# MATE_2024_float_layer_cake_footprint_v1.net
KiCad netlist of a schematic drawn in EAGLE
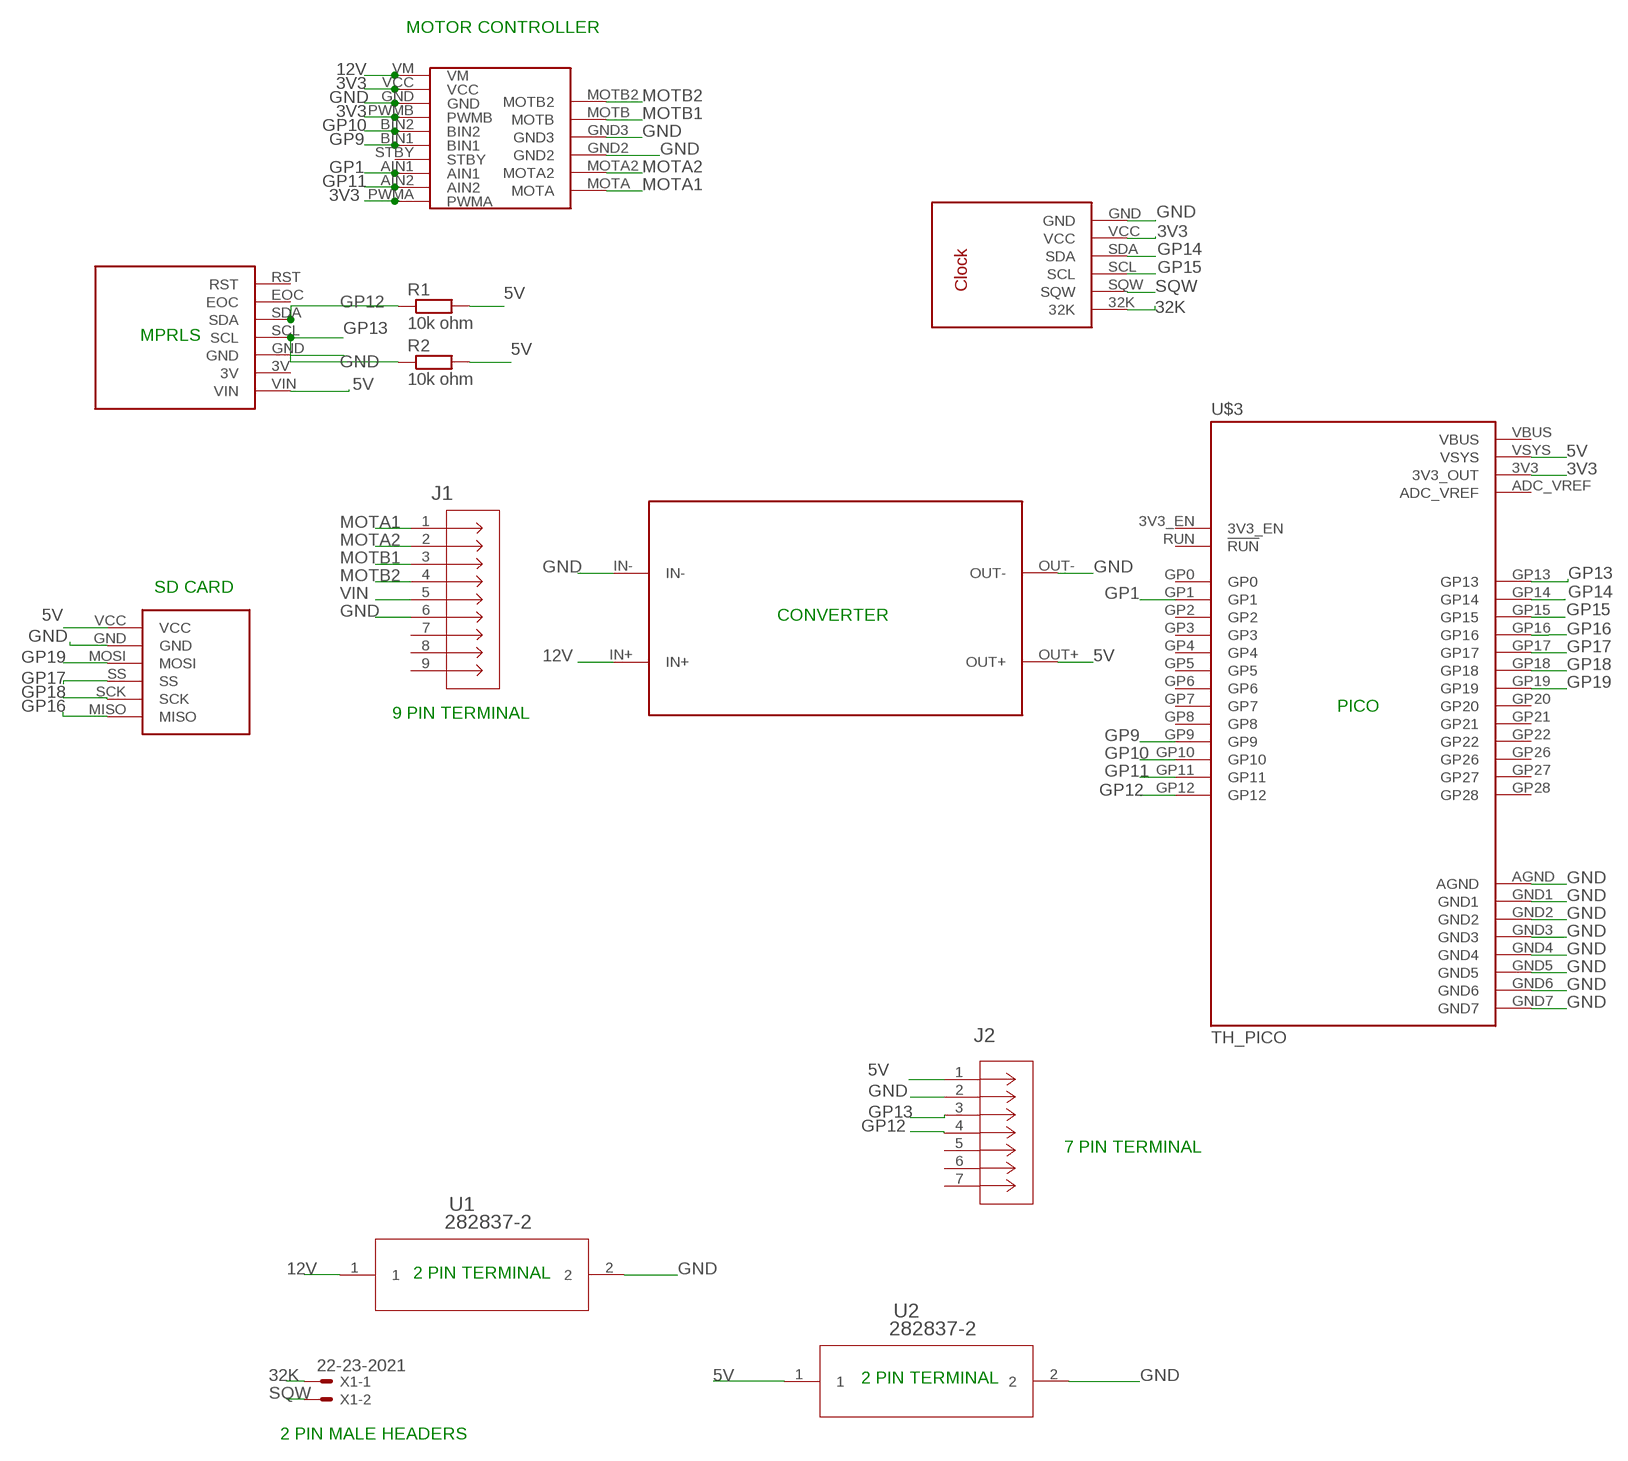
[diagram p0: schematic, sheet 1]

(export (version "E")
  (design (tool "Eeschema 10.0.6"))
  (components
    (comp (ref "J1")
      (value "282837-9")
      (footprint "eagle-import:CONN9_282837-9_TEC")
      (fields (field (name "COPYRIGHT") "Copyright (C) 2024 Ultra Librarian. All rights reserved."))
      (libsource (lib "eagle-import") (part "282837-9"))
    )
    (comp (ref "J2")
      (value "282837-7")
      (footprint "eagle-import:282837-7_TEC")
      (fields (field (name "COPYRIGHT") "Copyright (C) 2024 Ultra Librarian. All rights reserved."))
      (libsource (lib "eagle-import") (part "282837-7"))
    )
    (comp (ref "PRESSURE")
      (value "PRESSURE")
      (footprint "eagle-import:PRESSURE")
      (libsource (lib "eagle-import") (part "PRESSURE"))
    )
    (comp (ref "R1")
      (value "10k ohm")
      (footprint "eagle-import:0204_7")
      (libsource (lib "eagle-import") (part "R-EU_0204/7"))
    )
    (comp (ref "R2")
      (value "10k ohm")
      (footprint "eagle-import:0204_7")
      (libsource (lib "eagle-import") (part "R-EU_0204/7"))
    )
    (comp (ref "U$1")
      (value "CONVERTER")
      (footprint "eagle-import:CONVERTER")
      (libsource (lib "eagle-import") (part "CONVERTER"))
    )
    (comp (ref "U$2")
      (value "STEPPERMOTOR")
      (footprint "eagle-import:STEPPERV2")
      (libsource (lib "eagle-import") (part "STEPPERMOTOR"))
    )
    (comp (ref "U$3")
      (value "TH_PICO")
      (footprint "eagle-import:TH_PICO")
      (libsource (lib "eagle-import") (part "TH_PICO"))
    )
    (comp (ref "U$5")
      (value "MICROSDCARD")
      (footprint "eagle-import:MICROSDCARD")
      (libsource (lib "eagle-import") (part "MICROSDCARD"))
    )
    (comp (ref "U$6")
      (value "CLOCKMODULE")
      (footprint "eagle-import:CLOCKMODULE")
      (libsource (lib "eagle-import") (part "CLOCKMODULE"))
    )
    (comp (ref "U1")
      (value "282837-2")
      (footprint "eagle-import:282837-2_TYC")
      (fields (field (name "COPYRIGHT") "Copyright (C) 2024 Ultra Librarian. All rights reserved."))
      (libsource (lib "eagle-import") (part "282837-2"))
    )
    (comp (ref "U2")
      (value "282837-2")
      (footprint "eagle-import:282837-2_TYC")
      (fields (field (name "COPYRIGHT") "Copyright (C) 2024 Ultra Librarian. All rights reserved."))
      (libsource (lib "eagle-import") (part "282837-2"))
    )
    (comp (ref "X1")
      (value "22-23-2021")
      (footprint "eagle-import:22-23-2021")
      (fields (field (name "MF") "MOLEX"))
      (libsource (lib "eagle-import") (part "22-23-2021"))
    )
  )
  (nets
    (net (code "1") (name "/3V3") (class "Default")
      (node (ref "U$2") (pin "PWMA") (pinfunction "PWMA_PWMA") (pintype "bidirectional"))
      (node (ref "U$2") (pin "PWMB") (pinfunction "PWMB_PWMB") (pintype "bidirectional"))
      (node (ref "U$2") (pin "VCC") (pinfunction "VCC_VCC") (pintype "bidirectional"))
      (node (ref "U$3") (pin "3V3") (pinfunction "3V3_OUT_3V3") (pintype "power_in"))
      (node (ref "U$6") (pin "VCC") (pinfunction "VCC_VCC") (pintype "bidirectional"))
    )
    (net (code "2") (name "/5V") (class "Default")
      (node (ref "J2") (pin "1") (pinfunction "1_1") (pintype "passive"))
      (node (ref "PRESSURE") (pin "VIN") (pinfunction "VIN_VIN") (pintype "bidirectional"))
      (node (ref "R1") (pin "2") (pinfunction "2_2") (pintype "passive"))
      (node (ref "R2") (pin "2") (pinfunction "2_2") (pintype "passive"))
      (node (ref "U$1") (pin "OUT+") (pinfunction "OUT+_OUT+") (pintype "bidirectional"))
      (node (ref "U$3") (pin "VSYS") (pinfunction "VSYS_VSYS") (pintype "power_in"))
      (node (ref "U$5") (pin "VCC") (pinfunction "VCC_VCC") (pintype "bidirectional"))
      (node (ref "U2") (pin "1") (pinfunction "1_1") (pintype "passive"))
    )
    (net (code "3") (name "/12V") (class "Default")
      (node (ref "U$1") (pin "IN+") (pinfunction "IN+_IN+") (pintype "bidirectional"))
      (node (ref "U$2") (pin "VM") (pinfunction "VM_VM") (pintype "bidirectional"))
      (node (ref "U1") (pin "1") (pinfunction "1_1") (pintype "passive"))
    )
    (net (code "4") (name "/32K") (class "Default")
      (node (ref "U$6") (pin "32K") (pinfunction "32K_32K") (pintype "bidirectional"))
      (node (ref "X1") (pin "1") (pinfunction "S_1") (pintype "passive"))
    )
    (net (code "5") (name "/ADC_VREF") (class "Default")
      (node (ref "U$3") (pin "ADC_VREF") (pinfunction "ADC_VREF_ADC_VREF") (pintype "power_in"))
    )
    (net (code "6") (name "/GND") (class "Default")
      (node (ref "J1") (pin "6") (pinfunction "6_6") (pintype "passive"))
      (node (ref "J2") (pin "2") (pinfunction "2_2") (pintype "passive"))
      (node (ref "PRESSURE") (pin "GND") (pinfunction "GND_GND") (pintype "bidirectional"))
      (node (ref "U$1") (pin "IN-") (pinfunction "IN-_IN-") (pintype "bidirectional"))
      (node (ref "U$1") (pin "OUT-") (pinfunction "OUT-_OUT-") (pintype "bidirectional"))
      (node (ref "U$2") (pin "GND") (pinfunction "GND_GND") (pintype "bidirectional"))
      (node (ref "U$2") (pin "GND2") (pinfunction "GND2_GND2") (pintype "bidirectional"))
      (node (ref "U$2") (pin "GND3") (pinfunction "GND3_GND3") (pintype "bidirectional"))
      (node (ref "U$3") (pin "AGND") (pinfunction "AGND_AGND") (pintype "power_in"))
      (node (ref "U$3") (pin "GND1") (pinfunction "GND1_GND1") (pintype "power_in"))
      (node (ref "U$3") (pin "GND2") (pinfunction "GND2_GND2") (pintype "power_in"))
      (node (ref "U$3") (pin "GND3") (pinfunction "GND3_GND3") (pintype "power_in"))
      (node (ref "U$3") (pin "GND4") (pinfunction "GND4_GND4") (pintype "power_in"))
      (node (ref "U$3") (pin "GND5") (pinfunction "GND5_GND5") (pintype "power_in"))
      (node (ref "U$3") (pin "GND6") (pinfunction "GND6_GND6") (pintype "power_in"))
      (node (ref "U$3") (pin "GND7") (pinfunction "GND7_GND7") (pintype "power_in"))
      (node (ref "U$5") (pin "GND") (pinfunction "GND_GND") (pintype "bidirectional"))
      (node (ref "U$6") (pin "GND") (pinfunction "GND_GND") (pintype "bidirectional"))
      (node (ref "U1") (pin "2") (pinfunction "2_2") (pintype "passive"))
      (node (ref "U2") (pin "2") (pinfunction "2_2") (pintype "passive"))
    )
    (net (code "7") (name "/GP1") (class "Default")
      (node (ref "U$2") (pin "AIN1") (pinfunction "AIN1_AIN1") (pintype "bidirectional"))
      (node (ref "U$3") (pin "GP1") (pinfunction "GP1_GP1") (pintype "bidirectional"))
    )
    (net (code "8") (name "/GP9") (class "Default")
      (node (ref "U$2") (pin "BIN1") (pinfunction "BIN1_BIN1") (pintype "bidirectional"))
      (node (ref "U$3") (pin "GP9") (pinfunction "GP9_GP9") (pintype "bidirectional"))
    )
    (net (code "9") (name "/GP10") (class "Default")
      (node (ref "U$2") (pin "BIN2") (pinfunction "BIN2_BIN2") (pintype "bidirectional"))
      (node (ref "U$3") (pin "GP10") (pinfunction "GP10_GP10") (pintype "bidirectional"))
    )
    (net (code "10") (name "/GP11") (class "Default")
      (node (ref "U$2") (pin "AIN2") (pinfunction "AIN2_AIN2") (pintype "bidirectional"))
      (node (ref "U$3") (pin "GP11") (pinfunction "GP11_GP11") (pintype "bidirectional"))
    )
    (net (code "11") (name "/GP12") (class "Default")
      (node (ref "J2") (pin "4") (pinfunction "4_4") (pintype "passive"))
      (node (ref "PRESSURE") (pin "SDA") (pinfunction "SDA_SDA") (pintype "bidirectional"))
      (node (ref "R1") (pin "1") (pinfunction "1_1") (pintype "passive"))
      (node (ref "U$3") (pin "GP12") (pinfunction "GP12_GP12") (pintype "bidirectional"))
    )
    (net (code "12") (name "/GP13") (class "Default")
      (node (ref "J2") (pin "3") (pinfunction "3_3") (pintype "passive"))
      (node (ref "PRESSURE") (pin "SCL") (pinfunction "SCL_SCL") (pintype "bidirectional"))
      (node (ref "R2") (pin "1") (pinfunction "1_1") (pintype "passive"))
      (node (ref "U$3") (pin "GP13") (pinfunction "GP13_GP13") (pintype "bidirectional"))
    )
    (net (code "13") (name "/GP14") (class "Default")
      (node (ref "U$3") (pin "GP14") (pinfunction "GP14_GP14") (pintype "bidirectional"))
      (node (ref "U$6") (pin "SDA") (pinfunction "SDA_SDA") (pintype "bidirectional"))
    )
    (net (code "14") (name "/GP15") (class "Default")
      (node (ref "U$3") (pin "GP15") (pinfunction "GP15_GP15") (pintype "bidirectional"))
      (node (ref "U$6") (pin "SCL") (pinfunction "SCL_SCL") (pintype "bidirectional"))
    )
    (net (code "15") (name "/GP16") (class "Default")
      (node (ref "U$3") (pin "GP16") (pinfunction "GP16_GP16") (pintype "bidirectional"))
      (node (ref "U$5") (pin "MISO") (pinfunction "MISO_MISO") (pintype "bidirectional"))
    )
    (net (code "16") (name "/GP17") (class "Default")
      (node (ref "U$3") (pin "GP17") (pinfunction "GP17_GP17") (pintype "bidirectional"))
      (node (ref "U$5") (pin "SS") (pinfunction "SS_SS") (pintype "bidirectional"))
    )
    (net (code "17") (name "/GP18") (class "Default")
      (node (ref "U$3") (pin "GP18") (pinfunction "GP18_GP18") (pintype "bidirectional"))
      (node (ref "U$5") (pin "SCK") (pinfunction "SCK_SCK") (pintype "bidirectional"))
    )
    (net (code "18") (name "/GP19") (class "Default")
      (node (ref "U$3") (pin "GP19") (pinfunction "GP19_GP19") (pintype "bidirectional"))
      (node (ref "U$5") (pin "MOSI") (pinfunction "MOSI_MOSI") (pintype "bidirectional"))
    )
    (net (code "19") (name "/MOTA1") (class "Default")
      (node (ref "J1") (pin "1") (pinfunction "1_1") (pintype "passive"))
      (node (ref "U$2") (pin "MOTA") (pinfunction "MOTA_MOTA") (pintype "bidirectional"))
    )
    (net (code "20") (name "/MOTA2") (class "Default")
      (node (ref "J1") (pin "2") (pinfunction "2_2") (pintype "passive"))
      (node (ref "U$2") (pin "MOTA2") (pinfunction "MOTA2_MOTA2") (pintype "bidirectional"))
    )
    (net (code "21") (name "/MOTB1") (class "Default")
      (node (ref "J1") (pin "3") (pinfunction "3_3") (pintype "passive"))
      (node (ref "U$2") (pin "MOTB") (pinfunction "MOTB_MOTB") (pintype "bidirectional"))
    )
    (net (code "22") (name "/MOTB2") (class "Default")
      (node (ref "J1") (pin "4") (pinfunction "4_4") (pintype "passive"))
      (node (ref "U$2") (pin "MOTB2") (pinfunction "MOTB2_MOTB2") (pintype "bidirectional"))
    )
    (net (code "23") (name "/SQW") (class "Default")
      (node (ref "U$6") (pin "SQW") (pinfunction "SQW_SQW") (pintype "bidirectional"))
      (node (ref "X1") (pin "2") (pinfunction "S_2") (pintype "passive"))
    )
    (net (code "24") (name "/VBUS") (class "Default")
      (node (ref "U$3") (pin "VBUS") (pinfunction "VBUS_VBUS") (pintype "power_in"))
    )
    (net (code "25") (name "/VIN") (class "Default")
      (node (ref "J1") (pin "5") (pinfunction "5_5") (pintype "passive"))
    )
    (net (code "26") (name "unconnected-(J1-Pad7)") (class "Default")
      (node (ref "J1") (pin "7") (pinfunction "7_7") (pintype "passive"))
    )
    (net (code "27") (name "unconnected-(J1-Pad8)") (class "Default")
      (node (ref "J1") (pin "8") (pinfunction "8_8") (pintype "passive"))
    )
    (net (code "28") (name "unconnected-(J1-Pad9)") (class "Default")
      (node (ref "J1") (pin "9") (pinfunction "9_9") (pintype "passive"))
    )
    (net (code "29") (name "unconnected-(J2-Pad5)") (class "Default")
      (node (ref "J2") (pin "5") (pinfunction "5_5") (pintype "passive"))
    )
    (net (code "30") (name "unconnected-(J2-Pad6)") (class "Default")
      (node (ref "J2") (pin "6") (pinfunction "6_6") (pintype "passive"))
    )
    (net (code "31") (name "unconnected-(J2-Pad7)") (class "Default")
      (node (ref "J2") (pin "7") (pinfunction "7_7") (pintype "passive"))
    )
    (net (code "32") (name "unconnected-(PRESSURE-Pad3V)") (class "Default")
      (node (ref "PRESSURE") (pin "3V") (pinfunction "3V_3V") (pintype "bidirectional"))
    )
    (net (code "33") (name "unconnected-(PRESSURE-PadEOC)") (class "Default")
      (node (ref "PRESSURE") (pin "EOC") (pinfunction "EOC_EOC") (pintype "bidirectional"))
    )
    (net (code "34") (name "unconnected-(PRESSURE-PadRST)") (class "Default")
      (node (ref "PRESSURE") (pin "RST") (pinfunction "RST_RST") (pintype "bidirectional"))
    )
    (net (code "35") (name "unconnected-(U$2-PadSTBY)") (class "Default")
      (node (ref "U$2") (pin "STBY") (pinfunction "STBY_STBY") (pintype "bidirectional"))
    )
    (net (code "36") (name "unconnected-(U$3-Pad3V3_EN)") (class "Default")
      (node (ref "U$3") (pin "3V3_EN") (pinfunction "3V3_EN_3V3_EN") (pintype "input"))
    )
    (net (code "37") (name "unconnected-(U$3-PadGP0)") (class "Default")
      (node (ref "U$3") (pin "GP0") (pinfunction "GP0_GP0") (pintype "bidirectional"))
    )
    (net (code "38") (name "unconnected-(U$3-PadGP2)") (class "Default")
      (node (ref "U$3") (pin "GP2") (pinfunction "GP2_GP2") (pintype "bidirectional"))
    )
    (net (code "39") (name "unconnected-(U$3-PadGP3)") (class "Default")
      (node (ref "U$3") (pin "GP3") (pinfunction "GP3_GP3") (pintype "bidirectional"))
    )
    (net (code "40") (name "unconnected-(U$3-PadGP4)") (class "Default")
      (node (ref "U$3") (pin "GP4") (pinfunction "GP4_GP4") (pintype "bidirectional"))
    )
    (net (code "41") (name "unconnected-(U$3-PadGP5)") (class "Default")
      (node (ref "U$3") (pin "GP5") (pinfunction "GP5_GP5") (pintype "bidirectional"))
    )
    (net (code "42") (name "unconnected-(U$3-PadGP6)") (class "Default")
      (node (ref "U$3") (pin "GP6") (pinfunction "GP6_GP6") (pintype "bidirectional"))
    )
    (net (code "43") (name "unconnected-(U$3-PadGP7)") (class "Default")
      (node (ref "U$3") (pin "GP7") (pinfunction "GP7_GP7") (pintype "bidirectional"))
    )
    (net (code "44") (name "unconnected-(U$3-PadGP8)") (class "Default")
      (node (ref "U$3") (pin "GP8") (pinfunction "GP8_GP8") (pintype "bidirectional"))
    )
    (net (code "45") (name "unconnected-(U$3-PadGP20)") (class "Default")
      (node (ref "U$3") (pin "GP20") (pinfunction "GP20_GP20") (pintype "bidirectional"))
    )
    (net (code "46") (name "unconnected-(U$3-PadGP21)") (class "Default")
      (node (ref "U$3") (pin "GP21") (pinfunction "GP21_GP21") (pintype "bidirectional"))
    )
    (net (code "47") (name "unconnected-(U$3-PadGP22)") (class "Default")
      (node (ref "U$3") (pin "GP22") (pinfunction "GP22_GP22") (pintype "bidirectional"))
    )
    (net (code "48") (name "unconnected-(U$3-PadGP26)") (class "Default")
      (node (ref "U$3") (pin "GP26") (pinfunction "GP26_GP26") (pintype "bidirectional"))
    )
    (net (code "49") (name "unconnected-(U$3-PadGP27)") (class "Default")
      (node (ref "U$3") (pin "GP27") (pinfunction "GP27_GP27") (pintype "bidirectional"))
    )
    (net (code "50") (name "unconnected-(U$3-PadGP28)") (class "Default")
      (node (ref "U$3") (pin "GP28") (pinfunction "GP28_GP28") (pintype "bidirectional"))
    )
    (net (code "51") (name "unconnected-(U$3-~{RUN}-PadRUN)") (class "Default")
      (node (ref "U$3") (pin "RUN") (pinfunction "~{RUN}_RUN") (pintype "input"))
    )
  )
)
